# Top_View.net
KiCad netlist of a schematic drawn in Altium Designer
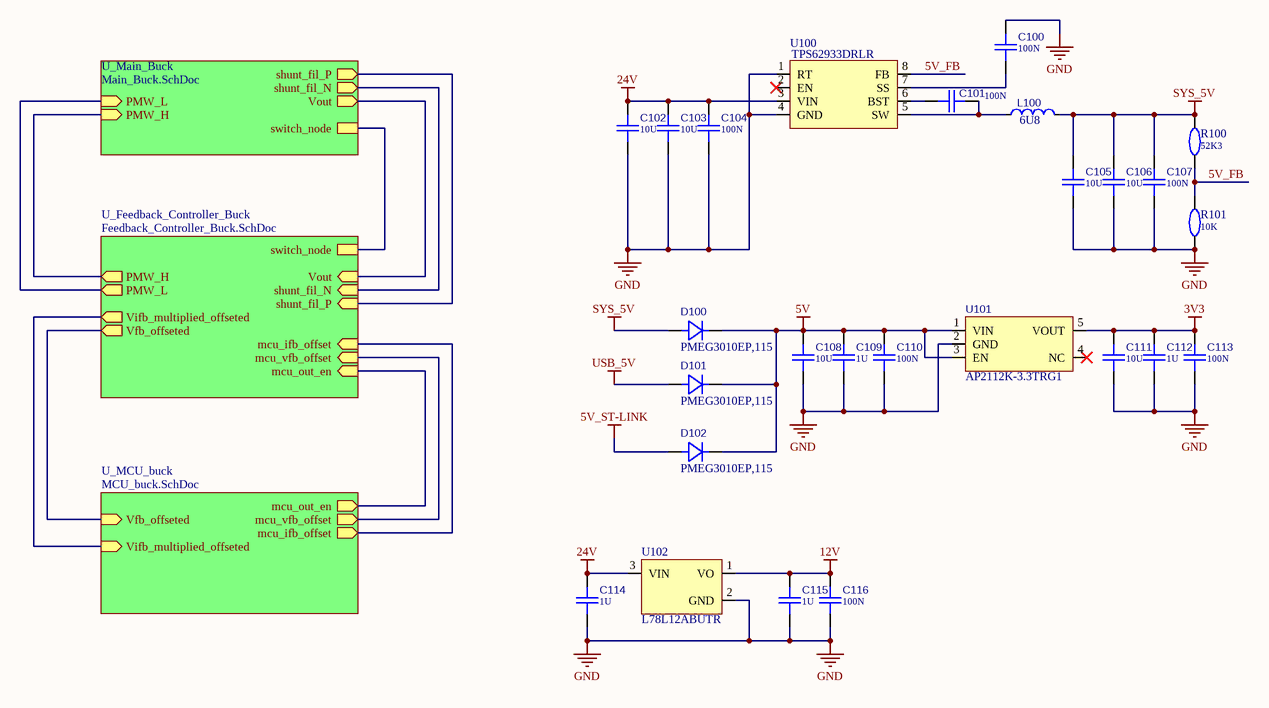
[diagram p0: Top_View.SchDoc]

(export (version "E")
  (design (tool "Eeschema 10.0.6"))
  (components
    (comp (ref "C100")
      (value "100N")
      (footprint "CAP_0402")
      (description "CAP 100N 0402 X7R 50V 10%")
      (fields (field (name "PART NUMBER") "UMK105B7104KV-FR") (field (name "Comment") "CAPACITOR"))
      (libsource (lib "Altium_Library") (part "CAPACITOR"))
    )
    (comp (ref "C101")
      (value "100N")
      (footprint "CAP_0402")
      (description "CAP 100N 0402 X7R 50V 10%")
      (fields (field (name "PART NUMBER") "UMK105B7104KV-FR") (field (name "Comment") "CAPACITOR"))
      (libsource (lib "Altium_Library") (part "CAPACITOR"))
    )
    (comp (ref "C102")
      (value "10U")
      (footprint "CAP_1210")
      (description "CAP 10U 1210 X7R 50V 10%")
      (fields (field (name "PART NUMBER") "UMK325AB7106KM-T") (field (name "Comment") "CAPACITOR"))
      (libsource (lib "Altium_Library") (part "CAPACITOR"))
    )
    (comp (ref "C103")
      (value "10U")
      (footprint "CAP_1210")
      (description "CAP 10U 1210 X7R 50V 10%")
      (fields (field (name "PART NUMBER") "UMK325AB7106KM-T") (field (name "Comment") "CAPACITOR"))
      (libsource (lib "Altium_Library") (part "CAPACITOR"))
    )
    (comp (ref "C104")
      (value "100N")
      (footprint "CAP_0402")
      (description "CAP 100N 0402 X7R 50V 10%")
      (fields (field (name "PART NUMBER") "UMK105B7104KV-FR") (field (name "Comment") "CAPACITOR"))
      (libsource (lib "Altium_Library") (part "CAPACITOR"))
    )
    (comp (ref "C105")
      (value "10U")
      (footprint "CAP_1210")
      (description "CAP 10U 1210 X7R 50V 10%")
      (fields (field (name "PART NUMBER") "UMK325AB7106KM-T") (field (name "Comment") "CAPACITOR"))
      (libsource (lib "Altium_Library") (part "CAPACITOR"))
    )
    (comp (ref "C106")
      (value "10U")
      (footprint "CAP_1210")
      (description "CAP 10U 1210 X7R 50V 10%")
      (fields (field (name "PART NUMBER") "UMK325AB7106KM-T") (field (name "Comment") "CAPACITOR"))
      (libsource (lib "Altium_Library") (part "CAPACITOR"))
    )
    (comp (ref "C107")
      (value "100N")
      (footprint "CAP_0402")
      (description "CAP 100N 0402 X7R 50V 10%")
      (fields (field (name "PART NUMBER") "UMK105B7104KV-FR") (field (name "Comment") "CAPACITOR"))
      (libsource (lib "Altium_Library") (part "CAPACITOR"))
    )
    (comp (ref "C108")
      (value "10U")
      (footprint "CAP_1210")
      (description "CAP 10U 1210 X7R 50V 10%")
      (fields (field (name "PART NUMBER") "UMK325AB7106KM-T") (field (name "Comment") "CAPACITOR"))
      (libsource (lib "Altium_Library") (part "CAPACITOR"))
    )
    (comp (ref "C109")
      (value "1U")
      (footprint "CAP_0603")
      (description "CAP 1U 0603 X7R 25V 10%")
      (fields (field (name "PART NUMBER") "TMK107AB7105KAHT") (field (name "Comment") "CAPACITOR"))
      (libsource (lib "Altium_Library") (part "CAPACITOR"))
    )
    (comp (ref "C110")
      (value "100N")
      (footprint "CAP_0402")
      (description "CAP 100N 0402 X7R 50V 10%")
      (fields (field (name "PART NUMBER") "UMK105B7104KV-FR") (field (name "Comment") "CAPACITOR"))
      (libsource (lib "Altium_Library") (part "CAPACITOR"))
    )
    (comp (ref "C111")
      (value "10U")
      (footprint "CAP_1210")
      (description "CAP 10U 1210 X7R 50V 10%")
      (fields (field (name "PART NUMBER") "UMK325AB7106KM-T") (field (name "Comment") "CAPACITOR"))
      (libsource (lib "Altium_Library") (part "CAPACITOR"))
    )
    (comp (ref "C112")
      (value "1U")
      (footprint "CAP_0603")
      (description "CAP 1U 0603 X7R 25V 10%")
      (fields (field (name "PART NUMBER") "TMK107AB7105KAHT") (field (name "Comment") "CAPACITOR"))
      (libsource (lib "Altium_Library") (part "CAPACITOR"))
    )
    (comp (ref "C113")
      (value "100N")
      (footprint "CAP_0402")
      (description "CAP 100N 0402 X7R 50V 10%")
      (fields (field (name "PART NUMBER") "UMK105B7104KV-FR") (field (name "Comment") "CAPACITOR"))
      (libsource (lib "Altium_Library") (part "CAPACITOR"))
    )
    (comp (ref "C114")
      (value "1U")
      (footprint "CAP_0603")
      (description "CAP 1U 0603 X7R 25V 10%")
      (fields (field (name "PART NUMBER") "TMK107AB7105KAHT") (field (name "Comment") "CAPACITOR"))
      (libsource (lib "Altium_Library") (part "CAPACITOR"))
    )
    (comp (ref "C115")
      (value "1U")
      (footprint "CAP_0603")
      (description "CAP 1U 0603 X7R 25V 10%")
      (fields (field (name "PART NUMBER") "TMK107AB7105KAHT") (field (name "Comment") "CAPACITOR"))
      (libsource (lib "Altium_Library") (part "CAPACITOR"))
    )
    (comp (ref "C116")
      (value "100N")
      (footprint "CAP_0402")
      (description "CAP 100N 0402 X7R 50V 10%")
      (fields (field (name "PART NUMBER") "UMK105B7104KV-FR") (field (name "Comment") "CAPACITOR"))
      (libsource (lib "Altium_Library") (part "CAPACITOR"))
    )
    (comp (ref "D100")
      (value "PMEG3010EP,115")
      (footprint "SOD-128")
      (description "DIODE PMEG3010EP,115 SOD-128  Schottky 30V 1A")
      (fields (field (name "VOLTAGE") "30V") (field (name "Comment") "DIODE"))
      (libsource (lib "Altium_Library") (part "DIODE"))
    )
    (comp (ref "D101")
      (value "PMEG3010EP,115")
      (footprint "SOD-128")
      (description "DIODE PMEG3010EP,115 SOD-128  Schottky 30V 1A")
      (fields (field (name "VOLTAGE") "30V") (field (name "Comment") "DIODE"))
      (libsource (lib "Altium_Library") (part "DIODE"))
    )
    (comp (ref "D102")
      (value "PMEG3010EP,115")
      (footprint "SOD-128")
      (description "DIODE PMEG3010EP,115 SOD-128  Schottky 30V 1A")
      (fields (field (name "VOLTAGE") "30V") (field (name "Comment") "DIODE"))
      (libsource (lib "Altium_Library") (part "DIODE"))
    )
    (comp (ref "L100")
      (value "6U8")
      (footprint "IND_LQH3NPN6R8MMEL")
      (description "IND 6U8 SMD_W3mm_L3mm 0.9A 1.04A")
      (fields (field (name "PART NUMBER") "LQH3NPN6R8MMEL") (field (name "Comment") "INDUCTOR"))
      (libsource (lib "Altium_Library") (part "INDUCTOR"))
    )
    (comp (ref "R100")
      (value "52K3")
      (footprint "RES_0603")
      (description "RES 52K3 0603 0.1% 0.1W 75V")
      (fields (field (name "PART NUMBER") "ERA3AEB5232V") (field (name "Comment") "RESISTOR"))
      (libsource (lib "Altium_Library") (part "RESISTOR"))
    )
    (comp (ref "R101")
      (value "10K")
      (footprint "RES_0603")
      (description "RES 10K 0603 0.1W 0.1% 75V")
      (fields (field (name "PART NUMBER") "ARG03BTC1002") (field (name "Comment") "RESISTOR"))
      (libsource (lib "Altium_Library") (part "RESISTOR"))
    )
    (comp (ref "U100")
      (value "TPS62933DRLR")
      (footprint "SOT-583")
      (description "IC TPS62933DRLR SOT-583 BUCK-CHIP")
      (fields (field (name "Comment") "BUCK-CHIP_8P"))
      (libsource (lib "Altium_Library") (part "BUCK-CHIP_8P"))
    )
    (comp (ref "U101")
      (value "AP2112K-3.3TRG1")
      (footprint "SOT-23-5")
      (description "LDO AP2112K-3.3TRG1 SOT-25-5 3.3V 600mA")
      (fields (field (name "Comment") "LDO_5P"))
      (libsource (lib "Altium_Library") (part "LDO_5P"))
    )
    (comp (ref "U102")
      (value "L78L12ABUTR")
      (footprint "SOT-98-3")
      (description "LDO L78L12ABUTR SOT-89-3 12V 100mA")
      (libsource (lib "Altium_Library") (part "LDO_3P"))
    )
  )
  (nets
    (net (code "1") (name "/5V_FB") (class "Default")
      (node (ref "R100") (pin "1") (pinfunction "1_1") (pintype "passive"))
      (node (ref "R101") (pin "2") (pinfunction "2_2") (pintype "passive"))
      (node (ref "U100") (pin "8") (pinfunction "FB_8") (pintype "passive"))
    )
    (net (code "13") (name "3V3") (class "Default")
      (node (ref "C111") (pin "2") (pinfunction "2_2") (pintype "passive"))
      (node (ref "C112") (pin "2") (pinfunction "2_2") (pintype "passive"))
      (node (ref "C113") (pin "2") (pinfunction "2_2") (pintype "passive"))
      (node (ref "U101") (pin "5") (pinfunction "VOUT_5") (pintype "passive"))
    )
    (net (code "14") (name "5V") (class "Default")
      (node (ref "C108") (pin "2") (pinfunction "2_2") (pintype "passive"))
      (node (ref "C109") (pin "2") (pinfunction "2_2") (pintype "passive"))
      (node (ref "C110") (pin "2") (pinfunction "2_2") (pintype "passive"))
      (node (ref "D100") (pin "1") (pinfunction "1_1") (pintype "passive"))
      (node (ref "D101") (pin "1") (pinfunction "1_1") (pintype "passive"))
      (node (ref "D102") (pin "1") (pinfunction "1_1") (pintype "passive"))
      (node (ref "U101") (pin "1") (pinfunction "VIN_1") (pintype "passive"))
      (node (ref "U101") (pin "3") (pinfunction "EN_3") (pintype "passive"))
    )
    (net (code "15") (name "5V_ST-LINK") (class "Default")
      (node (ref "D102") (pin "2") (pinfunction "2_2") (pintype "passive"))
    )
    (net (code "16") (name "12V") (class "Default")
      (node (ref "C115") (pin "2") (pinfunction "2_2") (pintype "passive"))
      (node (ref "C116") (pin "1") (pinfunction "1_1") (pintype "passive"))
      (node (ref "U102") (pin "1") (pinfunction "VO_1") (pintype "passive"))
    )
    (net (code "17") (name "24V") (class "Default")
      (node (ref "C102") (pin "2") (pinfunction "2_2") (pintype "passive"))
      (node (ref "C103") (pin "2") (pinfunction "2_2") (pintype "passive"))
      (node (ref "C104") (pin "2") (pinfunction "2_2") (pintype "passive"))
      (node (ref "C114") (pin "2") (pinfunction "2_2") (pintype "passive"))
      (node (ref "U100") (pin "3") (pinfunction "VIN_3") (pintype "passive"))
      (node (ref "U102") (pin "3") (pinfunction "VIN_3") (pintype "passive"))
    )
    (net (code "18") (name "GND") (class "Default")
      (node (ref "C100") (pin "2") (pinfunction "2_2") (pintype "passive"))
      (node (ref "C102") (pin "1") (pinfunction "1_1") (pintype "passive"))
      (node (ref "C103") (pin "1") (pinfunction "1_1") (pintype "passive"))
      (node (ref "C104") (pin "1") (pinfunction "1_1") (pintype "passive"))
      (node (ref "C105") (pin "1") (pinfunction "1_1") (pintype "passive"))
      (node (ref "C106") (pin "1") (pinfunction "1_1") (pintype "passive"))
      (node (ref "C107") (pin "1") (pinfunction "1_1") (pintype "passive"))
      (node (ref "C108") (pin "1") (pinfunction "1_1") (pintype "passive"))
      (node (ref "C109") (pin "1") (pinfunction "1_1") (pintype "passive"))
      (node (ref "C110") (pin "1") (pinfunction "1_1") (pintype "passive"))
      (node (ref "C111") (pin "1") (pinfunction "1_1") (pintype "passive"))
      (node (ref "C112") (pin "1") (pinfunction "1_1") (pintype "passive"))
      (node (ref "C113") (pin "1") (pinfunction "1_1") (pintype "passive"))
      (node (ref "C114") (pin "1") (pinfunction "1_1") (pintype "passive"))
      (node (ref "C115") (pin "1") (pinfunction "1_1") (pintype "passive"))
      (node (ref "C116") (pin "2") (pinfunction "2_2") (pintype "passive"))
      (node (ref "R101") (pin "1") (pinfunction "1_1") (pintype "passive"))
      (node (ref "U100") (pin "1") (pinfunction "RT_1") (pintype "passive"))
      (node (ref "U100") (pin "4") (pinfunction "GND_4") (pintype "passive"))
      (node (ref "U101") (pin "2") (pinfunction "GND_2") (pintype "passive"))
      (node (ref "U102") (pin "2") (pinfunction "GND_2") (pintype "passive"))
    )
    (net (code "19") (name "Net-(U100-BST)") (class "Default")
      (node (ref "C101") (pin "1") (pinfunction "1_1") (pintype "passive"))
      (node (ref "U100") (pin "6") (pinfunction "BST_6") (pintype "passive"))
    )
    (net (code "20") (name "Net-(U100-SS)") (class "Default")
      (node (ref "C100") (pin "1") (pinfunction "1_1") (pintype "passive"))
      (node (ref "U100") (pin "7") (pinfunction "SS_7") (pintype "passive"))
    )
    (net (code "21") (name "Net-(U100-SW)") (class "Default")
      (node (ref "C101") (pin "2") (pinfunction "2_2") (pintype "passive"))
      (node (ref "L100") (pin "1") (pinfunction "1_1") (pintype "passive"))
      (node (ref "U100") (pin "5") (pinfunction "SW_5") (pintype "passive"))
    )
    (net (code "22") (name "SYS_5V") (class "Default")
      (node (ref "C105") (pin "2") (pinfunction "2_2") (pintype "passive"))
      (node (ref "C106") (pin "2") (pinfunction "2_2") (pintype "passive"))
      (node (ref "C107") (pin "2") (pinfunction "2_2") (pintype "passive"))
      (node (ref "D100") (pin "2") (pinfunction "2_2") (pintype "passive"))
      (node (ref "L100") (pin "2") (pinfunction "2_2") (pintype "passive"))
      (node (ref "R100") (pin "2") (pinfunction "2_2") (pintype "passive"))
    )
    (net (code "23") (name "USB_5V") (class "Default")
      (node (ref "D101") (pin "2") (pinfunction "2_2") (pintype "passive"))
    )
    (net (code "24") (name "unconnected-(U100-EN-Pad2)") (class "Default")
      (node (ref "U100") (pin "2") (pinfunction "EN_2") (pintype "passive+no_connect"))
    )
    (net (code "25") (name "unconnected-(U101-NC-Pad4)") (class "Default")
      (node (ref "U101") (pin "4") (pinfunction "NC_4") (pintype "passive+no_connect"))
    )
  )
)
